# Filtre_PWM60Hz.net
KiCad netlist of a schematic drawn in Altium Designer
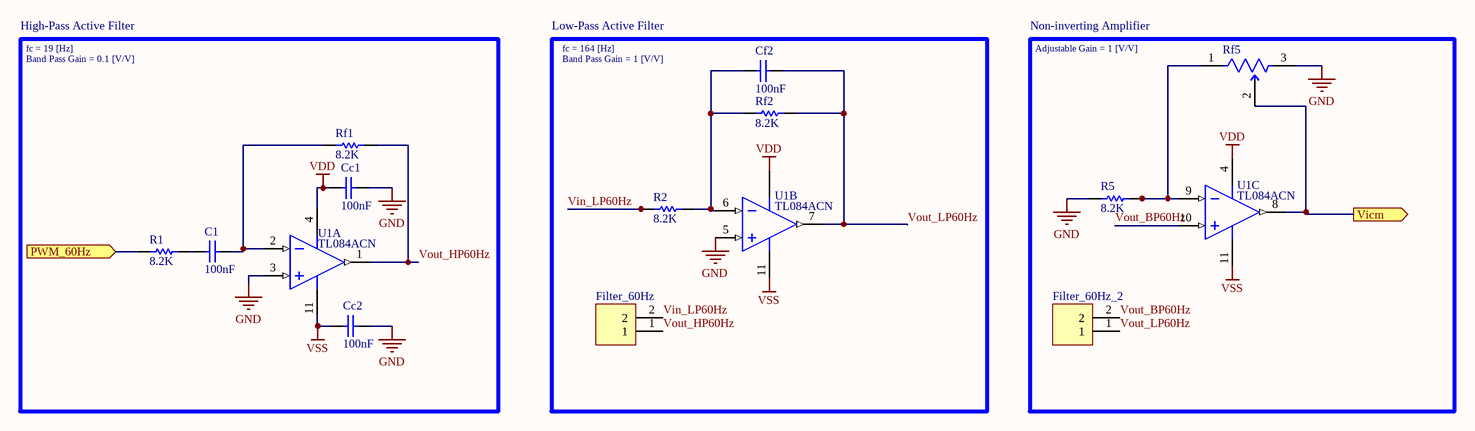
[diagram p0: Filtre_PWM60Hz.SchDoc]

(export (version "E")
  (design (tool "Eeschema 10.0.6"))
  (components
    (comp (ref "C1")
      (value "100nF")
      (footprint "condensateur 0.1uf 100mil")
      (description "Capacitor")
      (fields (field (name "Comment") "Cap") (field (name "PUBLISHER") "Altium Limited"))
      (libsource (lib "signal-generator") (part "Cap"))
    )
    (comp (ref "Cc1")
      (value "100nF")
      (footprint "condensateur 0.1uf 100mil")
      (description "Capacitor")
      (fields (field (name "Comment") "Cap") (field (name "PUBLISHER") "Altium Limited"))
      (libsource (lib "signal-generator") (part "Cap"))
    )
    (comp (ref "Cc2")
      (value "100nF")
      (footprint "condensateur 0.1uf 100mil")
      (description "Capacitor")
      (fields (field (name "Comment") "Cap") (field (name "PUBLISHER") "Altium Limited"))
      (libsource (lib "signal-generator") (part "Cap"))
    )
    (comp (ref "Cf2")
      (value "100nF")
      (footprint "condensateur 0.1uf 100mil")
      (description "Capacitor")
      (fields (field (name "Comment") "Cap") (field (name "PUBLISHER") "Altium Limited"))
      (libsource (lib "signal-generator") (part "Cap"))
    )
    (comp (ref "Filter_60Hz")
      (value "Jumper")
      (footprint "Header 2P 100mil")
      (description "CONN HEADER VERT 3POS 2.54MM")
      (fields (field (name "PUBLISHER") "Altium Limited"))
      (libsource (lib "PCB_Alimentation_équipe1") (part "header 2 pin_UL"))
    )
    (comp (ref "Filter_60Hz_2")
      (value "Jumper")
      (footprint "Header 2P 100mil")
      (description "CONN HEADER VERT 3POS 2.54MM")
      (fields (field (name "PUBLISHER") "Altium Limited"))
      (libsource (lib "PCB_Alimentation_équipe1") (part "header 2 pin_UL"))
    )
    (comp (ref "R1")
      (value "8.2K")
      (footprint "Resistor_Axial 0.4")
      (description "Resistor")
      (fields (field (name "Comment") "Res1") (field (name "PUBLISHER") "Altium Limited"))
      (libsource (lib "signal-generator") (part "Res1"))
    )
    (comp (ref "R2")
      (value "8.2K")
      (footprint "Resistor_Axial 0.4")
      (description "Resistor")
      (fields (field (name "Comment") "Res1") (field (name "PUBLISHER") "Altium Limited"))
      (libsource (lib "signal-generator") (part "Res1"))
    )
    (comp (ref "R5")
      (value "8.2K")
      (footprint "Resistor_Axial 0.4")
      (description "Resistor")
      (fields (field (name "Comment") "Res1") (field (name "PUBLISHER") "Altium Limited"))
      (libsource (lib "signal-generator") (part "Res1"))
    )
    (comp (ref "Rf1")
      (value "8.2K")
      (footprint "Resistor_Axial 0.4")
      (description "Resistor")
      (fields (field (name "Comment") "Res1") (field (name "PUBLISHER") "Altium Limited"))
      (libsource (lib "signal-generator") (part "Res1"))
    )
    (comp (ref "Rf2")
      (value "8.2K")
      (footprint "Resistor_Axial 0.4")
      (description "Resistor")
      (fields (field (name "Comment") "Res1") (field (name "PUBLISHER") "Altium Limited"))
      (libsource (lib "signal-generator") (part "Res1"))
    )
    (comp (ref "Rf5")
      (value "67WR100KLF")
      (footprint "FP-67W-MFG")
      (description "TRIMMER 100K OHM 0.5W PC PIN TOP")
      (fields (field (name "TOLERANCE") "10%"))
      (libsource (lib "Altium Content Vault") (part "a77ee20e32664c43a3a1dd5392b6021"))
    )
    (comp (ref "U1")
      (value "TL084ACN")
      (footprint "N0014A")
      (description "JFET-Input Operational Amplifier, 7 to 36 V, 0 to 70 degC, 14-pin DIP (N14), Pb-Free (RoHS)")
      (fields (field (name "MANUFACTURER") "Texas Instruments"))
      (libsource (lib "Altium Content Vault") (part "TI-TLXX4X_MC3403-X14"))
    )
  )
  (nets
    (net (code "1") (name "/PWM_60Hz") (class "Default")
      (node (ref "R1") (pin "1") (pinfunction "1_1") (pintype "passive"))
    )
    (net (code "2") (name "/Vicm") (class "Default")
      (node (ref "Rf5") (pin "2") (pinfunction "2_2") (pintype "passive"))
      (node (ref "U1") (pin "8") (pinfunction "OUT3_8") (pintype "output"))
    )
    (net (code "3") (name "/Vin_LP60Hz") (class "Default")
      (node (ref "Filter_60Hz") (pin "2") (pinfunction "2_2") (pintype "passive"))
      (node (ref "R2") (pin "1") (pinfunction "1_1") (pintype "passive"))
    )
    (net (code "4") (name "/Vout_BP60Hz") (class "Default")
      (node (ref "Filter_60Hz_2") (pin "2") (pinfunction "2_2") (pintype "passive"))
      (node (ref "U1") (pin "10") (pinfunction "IN3+_10") (pintype "input"))
    )
    (net (code "5") (name "/Vout_HP60Hz") (class "Default")
      (node (ref "Filter_60Hz") (pin "1") (pinfunction "1_1") (pintype "passive"))
      (node (ref "Rf1") (pin "2") (pinfunction "2_2") (pintype "passive"))
      (node (ref "U1") (pin "1") (pinfunction "OUT1_1") (pintype "output"))
    )
    (net (code "6") (name "/Vout_LP60Hz") (class "Default")
      (node (ref "Cf2") (pin "2") (pinfunction "2_2") (pintype "passive"))
      (node (ref "Filter_60Hz_2") (pin "1") (pinfunction "1_1") (pintype "passive"))
      (node (ref "Rf2") (pin "2") (pinfunction "2_2") (pintype "passive"))
      (node (ref "U1") (pin "7") (pinfunction "OUT2_7") (pintype "output"))
    )
    (net (code "7") (name "GND") (class "Default")
      (node (ref "Cc1") (pin "2") (pinfunction "2_2") (pintype "passive"))
      (node (ref "Cc2") (pin "2") (pinfunction "2_2") (pintype "passive"))
      (node (ref "R5") (pin "1") (pinfunction "1_1") (pintype "passive"))
      (node (ref "Rf5") (pin "3") (pinfunction "3_3") (pintype "passive"))
      (node (ref "U1") (pin "3") (pinfunction "IN1+_3") (pintype "input"))
      (node (ref "U1") (pin "5") (pinfunction "IN2+_5") (pintype "input"))
    )
    (net (code "8") (name "Net-(C1-Pad1)") (class "Default")
      (node (ref "C1") (pin "1") (pinfunction "1_1") (pintype "passive"))
      (node (ref "R1") (pin "2") (pinfunction "2_2") (pintype "passive"))
    )
    (net (code "9") (name "Net-(U1A-IN1-)") (class "Default")
      (node (ref "C1") (pin "2") (pinfunction "2_2") (pintype "passive"))
      (node (ref "Rf1") (pin "1") (pinfunction "1_1") (pintype "passive"))
      (node (ref "U1") (pin "2") (pinfunction "IN1-_2") (pintype "input"))
    )
    (net (code "10") (name "Net-(U1B-IN2-)") (class "Default")
      (node (ref "Cf2") (pin "1") (pinfunction "1_1") (pintype "passive"))
      (node (ref "R2") (pin "2") (pinfunction "2_2") (pintype "passive"))
      (node (ref "Rf2") (pin "1") (pinfunction "1_1") (pintype "passive"))
      (node (ref "U1") (pin "6") (pinfunction "IN2-_6") (pintype "input"))
    )
    (net (code "11") (name "Net-(U1C-IN3-)") (class "Default")
      (node (ref "R5") (pin "2") (pinfunction "2_2") (pintype "passive"))
      (node (ref "Rf5") (pin "1") (pinfunction "1_1") (pintype "passive"))
      (node (ref "U1") (pin "9") (pinfunction "IN3-_9") (pintype "input"))
    )
    (net (code "12") (name "VDD") (class "Default")
      (node (ref "Cc1") (pin "1") (pinfunction "1_1") (pintype "passive"))
      (node (ref "U1") (pin "4") (pinfunction "VCC+_4") (pintype "power_in"))
    )
    (net (code "13") (name "VSS") (class "Default")
      (node (ref "Cc2") (pin "1") (pinfunction "1_1") (pintype "passive"))
      (node (ref "U1") (pin "11") (pinfunction "VCC-_11") (pintype "power_in"))
    )
  )
)
